# Bi_Dir_Circuit.net
KiCad netlist of a schematic drawn in Altium Designer
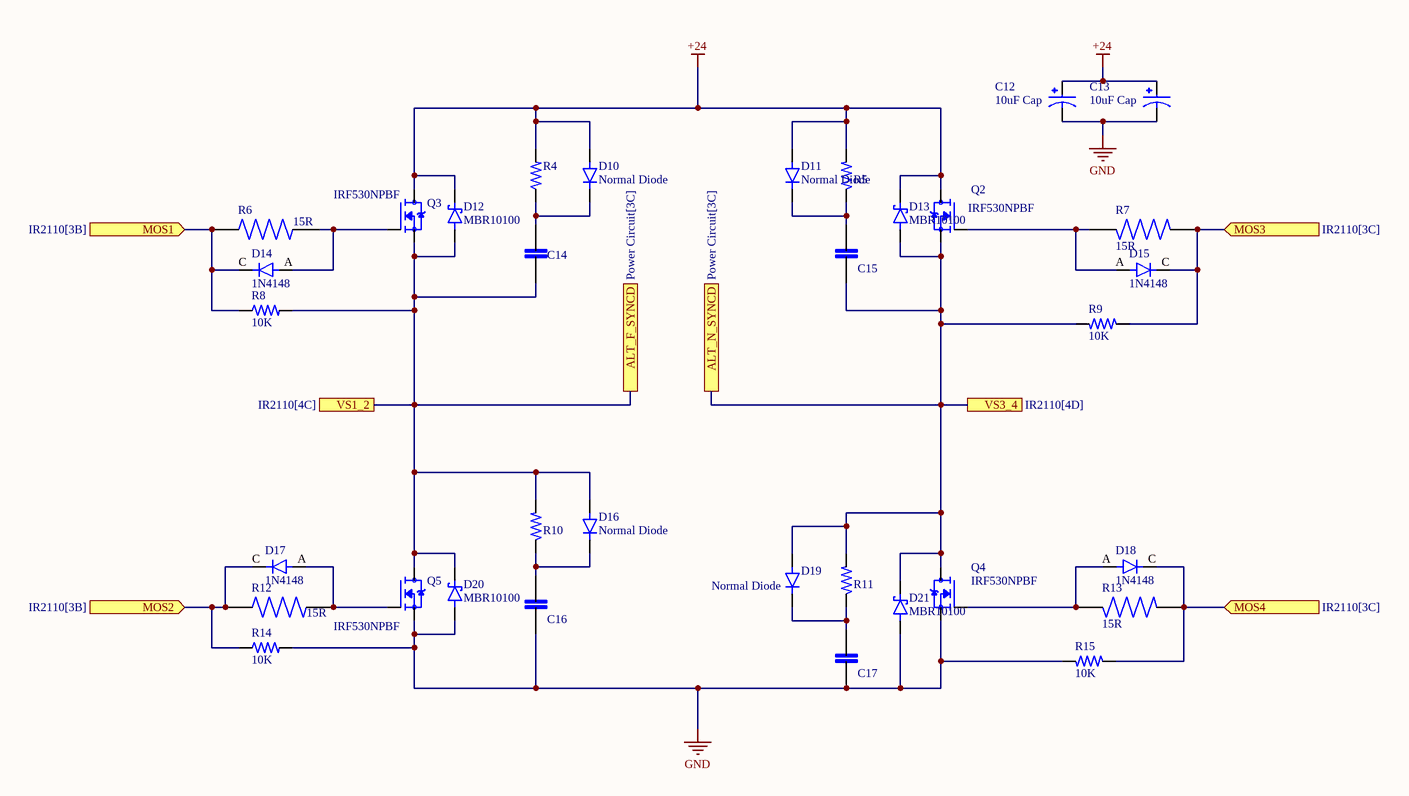
[diagram p0: Bi_Dir_Circuit.SchDoc]

(export (version "E")
  (design (tool "Eeschema 10.0.6"))
  (components
    (comp (ref "C12")
      (value "10uF Cap")
      (footprint "2200uF_Cap")
      (description "CAP ALUM 10UF 20% 50V RADIAL")
      (fields (field (name "MP") "ECE-A1HN100UI") (field (name "MF") "Panasonic"))
      (libsource (lib "MySCH_Library") (part "10uF Cap"))
    )
    (comp (ref "C13")
      (value "10uF Cap")
      (footprint "2200uF_Cap")
      (description "CAP ALUM 10UF 20% 50V RADIAL")
      (fields (field (name "MP") "ECE-A1HN100UI") (field (name "MF") "Panasonic"))
      (libsource (lib "MySCH_Library") (part "10uF Cap"))
    )
    (comp (ref "C14")
      (value "Ceramic Capacitor")
      (footprint "Ceramic Capacitor")
      (fields (field (name "MP") "LD051A121KAB2A") (field (name "MF") "AVX"))
      (libsource (lib "") (part "Ceramic Capacitor_1"))
    )
    (comp (ref "C15")
      (value "Ceramic Capacitor")
      (footprint "Ceramic Capacitor")
      (fields (field (name "MP") "LD051A121KAB2A") (field (name "MF") "AVX"))
      (libsource (lib "Capacitors Through Hole") (part "Ceramic Capacitor"))
    )
    (comp (ref "C16")
      (value "Ceramic Capacitor")
      (footprint "Ceramic Capacitor")
      (fields (field (name "MP") "LD051A121KAB2A") (field (name "MF") "AVX"))
      (libsource (lib "Capacitors Through Hole") (part "Ceramic Capacitor"))
    )
    (comp (ref "C17")
      (value "Ceramic Capacitor")
      (footprint "Ceramic Capacitor")
      (fields (field (name "MP") "LD051A121KAB2A") (field (name "MF") "AVX"))
      (libsource (lib "Capacitors Through Hole") (part "Ceramic Capacitor"))
    )
    (comp (ref "D10")
      (value "Normal Diode")
      (footprint "Common Trhough Hole")
      (fields (field (name "MF") "NTE Electronics, Inc.") (field (name "MP") "1N4007"))
      (libsource (lib "Diodes Through Hole") (part "Normal Diode"))
    )
    (comp (ref "D11")
      (value "Normal Diode")
      (footprint "Common Trhough Hole")
      (fields (field (name "MF") "NTE Electronics, Inc.") (field (name "MP") "1N4007"))
      (libsource (lib "Diodes Through Hole") (part "Normal Diode"))
    )
    (comp (ref "D12")
      (value "MBR10100")
      (footprint "MBR10100")
      (fields (field (name "MF") "Diodes Inc.") (field (name "MP") "1N5817-T"))
      (libsource (lib "Diodes Through Hole") (part "MBR10100"))
    )
    (comp (ref "D13")
      (value "MBR10100")
      (footprint "MBR10100")
      (fields (field (name "MF") "Diodes Inc.") (field (name "MP") "1N5817-T"))
      (libsource (lib "Diodes Through Hole") (part "MBR10100"))
    )
    (comp (ref "D14")
      (value "1N4148")
      (footprint "1N4007 DIODE")
      (description "Diode Standard 1000 V 1A Through Hole DO-41")
      (fields (field (name "MF") "NTE Electronics, Inc.") (field (name "MP") "1N4007"))
      (libsource (lib "MySCH_Library") (part "1N4007"))
    )
    (comp (ref "D15")
      (value "1N4148")
      (footprint "1N4007 DIODE")
      (description "Diode Standard 1000 V 1A Through Hole DO-41")
      (fields (field (name "MF") "NTE Electronics, Inc.") (field (name "MP") "1N4007"))
      (libsource (lib "MySCH_Library") (part "1N4007"))
    )
    (comp (ref "D16")
      (value "Normal Diode")
      (footprint "Common Trhough Hole")
      (fields (field (name "MF") "NTE Electronics, Inc.") (field (name "MP") "1N4007"))
      (libsource (lib "Diodes Through Hole") (part "Normal Diode"))
    )
    (comp (ref "D17")
      (value "1N4148")
      (footprint "1N4007 DIODE")
      (description "Diode Standard 1000 V 1A Through Hole DO-41")
      (fields (field (name "MF") "NTE Electronics, Inc.") (field (name "MP") "1N4007"))
      (libsource (lib "MySCH_Library") (part "1N4007"))
    )
    (comp (ref "D18")
      (value "1N4148")
      (footprint "1N4007 DIODE")
      (description "Diode Standard 1000 V 1A Through Hole DO-41")
      (fields (field (name "MF") "NTE Electronics, Inc.") (field (name "MP") "1N4007"))
      (libsource (lib "MySCH_Library") (part "1N4007"))
    )
    (comp (ref "D19")
      (value "Normal Diode")
      (footprint "Common Trhough Hole")
      (fields (field (name "MF") "NTE Electronics, Inc.") (field (name "MP") "1N4007"))
      (libsource (lib "Diodes Through Hole") (part "Normal Diode"))
    )
    (comp (ref "D20")
      (value "MBR10100")
      (footprint "MBR10100")
      (fields (field (name "MF") "Diodes Inc.") (field (name "MP") "1N5817-T"))
      (libsource (lib "Diodes Through Hole") (part "MBR10100"))
    )
    (comp (ref "D21")
      (value "MBR10100")
      (footprint "MBR10100")
      (fields (field (name "MF") "Diodes Inc.") (field (name "MP") "1N5817-T"))
      (libsource (lib "Diodes Through Hole") (part "MBR10100"))
    )
    (comp (ref "Q2")
      (value "IRF530NPBF")
      (footprint "IRF530N")
      (fields (field (name "MF") "Infineon Technologies"))
      (libsource (lib "MySCH_Library") (part "IRF530NPBF"))
    )
    (comp (ref "Q3")
      (value "IRF530NPBF")
      (footprint "IRF530N")
      (fields (field (name "MF") "Infineon Technologies"))
      (libsource (lib "MySCH_Library") (part "IRF530NPBF"))
    )
    (comp (ref "Q4")
      (value "IRF530NPBF")
      (footprint "IRF530N")
      (fields (field (name "MF") "Infineon Technologies"))
      (libsource (lib "MySCH_Library") (part "IRF530NPBF"))
    )
    (comp (ref "Q5")
      (value "IRF530NPBF")
      (footprint "IRF530N")
      (fields (field (name "MF") "Infineon Technologies"))
      (libsource (lib "MySCH_Library") (part "IRF530NPBF"))
    )
    (comp (ref "R4")
      (value "Resistor")
      (footprint "Resistor_Through Hole")
      (fields
        (field (name "MP") "2-2176053-0")
        (field (name "TOLERANCE") "1%")
        (field (name "MF") "TE Connectivity")
      )
      (libsource (lib "Resistors Through Hole") (part "Resistor"))
    )
    (comp (ref "R5")
      (value "Resistor")
      (footprint "Resistor_Through Hole")
      (fields
        (field (name "MP") "2-2176053-0")
        (field (name "TOLERANCE") "1%")
        (field (name "MF") "TE Connectivity")
      )
      (libsource (lib "Resistors Through Hole") (part "Resistor"))
    )
    (comp (ref "R6")
      (value "15R")
      (footprint "Resistor_Through Hole")
      (description "1.02 Ohms Â±1% 0.25W, 1/4W Through Hole Resistor Axial Metal Film")
      (fields (field (name "MP") "MFR-25FTE52-1R") (field (name "MF") "Yageo"))
      (libsource (lib "MySCH_Library") (part "Resistor_Through Hole"))
    )
    (comp (ref "R7")
      (value "15R")
      (footprint "Resistor_Through Hole")
      (description "1.02 Ohms Â±1% 0.25W, 1/4W Through Hole Resistor Axial Metal Film")
      (fields (field (name "MP") "MFR-25FTE52-1R") (field (name "MF") "Yageo"))
      (libsource (lib "MySCH_Library") (part "Resistor_Through Hole"))
    )
    (comp (ref "R8")
      (value "10K")
      (footprint "Resistor_Through Hole")
      (fields
        (field (name "MP") "2-2176053-0")
        (field (name "TOLERANCE") "1%")
        (field (name "MF") "TE Connectivity")
      )
      (libsource (lib "Resistors Through Hole") (part "Resistor"))
    )
    (comp (ref "R9")
      (value "10K")
      (footprint "Resistor_Through Hole")
      (fields
        (field (name "MP") "2-2176053-0")
        (field (name "TOLERANCE") "1%")
        (field (name "MF") "TE Connectivity")
      )
      (libsource (lib "Resistors Through Hole") (part "Resistor"))
    )
    (comp (ref "R10")
      (value "Resistor")
      (footprint "Resistor_Through Hole")
      (fields
        (field (name "MP") "2-2176053-0")
        (field (name "TOLERANCE") "1%")
        (field (name "MF") "TE Connectivity")
      )
      (libsource (lib "Resistors Through Hole") (part "Resistor"))
    )
    (comp (ref "R11")
      (value "Resistor")
      (footprint "Resistor_Through Hole")
      (fields
        (field (name "MP") "2-2176053-0")
        (field (name "TOLERANCE") "1%")
        (field (name "MF") "TE Connectivity")
      )
      (libsource (lib "Resistors Through Hole") (part "Resistor"))
    )
    (comp (ref "R12")
      (value "15R")
      (footprint "Resistor_Through Hole")
      (description "1.02 Ohms Â±1% 0.25W, 1/4W Through Hole Resistor Axial Metal Film")
      (fields (field (name "MP") "MFR-25FTE52-1R") (field (name "MF") "Yageo"))
      (libsource (lib "MySCH_Library") (part "Resistor_Through Hole"))
    )
    (comp (ref "R13")
      (value "15R")
      (footprint "Resistor_Through Hole")
      (description "1.02 Ohms Â±1% 0.25W, 1/4W Through Hole Resistor Axial Metal Film")
      (fields (field (name "MP") "MFR-25FTE52-1R") (field (name "MF") "Yageo"))
      (libsource (lib "MySCH_Library") (part "Resistor_Through Hole"))
    )
    (comp (ref "R14")
      (value "10K")
      (footprint "Resistor_Through Hole")
      (fields
        (field (name "MP") "2-2176053-0")
        (field (name "TOLERANCE") "1%")
        (field (name "MF") "TE Connectivity")
      )
      (libsource (lib "Resistors Through Hole") (part "Resistor"))
    )
    (comp (ref "R15")
      (value "10K")
      (footprint "Resistor_Through Hole")
      (fields
        (field (name "MP") "2-2176053-0")
        (field (name "TOLERANCE") "1%")
        (field (name "MF") "TE Connectivity")
      )
      (libsource (lib "Resistors Through Hole") (part "Resistor"))
    )
  )
  (nets
    (net (code "1") (name "+24") (class "Default")
      (node (ref "C12") (pin "P") (pinfunction "P_P") (pintype "passive"))
      (node (ref "C13") (pin "P") (pinfunction "P_P") (pintype "passive"))
      (node (ref "D10") (pin "2") (pinfunction "A_2") (pintype "passive"))
      (node (ref "D11") (pin "2") (pinfunction "A_2") (pintype "passive"))
      (node (ref "D12") (pin "1") (pinfunction "K_1") (pintype "passive"))
      (node (ref "D13") (pin "1") (pinfunction "K_1") (pintype "passive"))
      (node (ref "Q2") (pin "2") (pinfunction "D_2") (pintype "passive"))
      (node (ref "Q3") (pin "2") (pinfunction "D_2") (pintype "passive"))
      (node (ref "R4") (pin "2") (pinfunction "2_2") (pintype "passive"))
      (node (ref "R5") (pin "2") (pinfunction "2_2") (pintype "passive"))
    )
    (net (code "2") (name "/ALT_F_SYNCD") (class "Default")
      (node (ref "C14") (pin "1") (pinfunction "1_1") (pintype "passive"))
      (node (ref "D12") (pin "3") (pinfunction "A_3") (pintype "passive"))
      (node (ref "D16") (pin "2") (pinfunction "A_2") (pintype "passive"))
      (node (ref "D20") (pin "1") (pinfunction "K_1") (pintype "passive"))
      (node (ref "Q3") (pin "3") (pinfunction "S_3") (pintype "passive"))
      (node (ref "Q5") (pin "2") (pinfunction "D_2") (pintype "passive"))
      (node (ref "R10") (pin "2") (pinfunction "2_2") (pintype "passive"))
      (node (ref "R8") (pin "2") (pinfunction "2_2") (pintype "passive"))
    )
    (net (code "3") (name "/ALT_N_SYNCD") (class "Default")
      (node (ref "C15") (pin "1") (pinfunction "1_1") (pintype "passive"))
      (node (ref "D13") (pin "3") (pinfunction "A_3") (pintype "passive"))
      (node (ref "D19") (pin "2") (pinfunction "A_2") (pintype "passive"))
      (node (ref "D21") (pin "1") (pinfunction "K_1") (pintype "passive"))
      (node (ref "Q2") (pin "3") (pinfunction "S_3") (pintype "passive"))
      (node (ref "Q4") (pin "2") (pinfunction "D_2") (pintype "passive"))
      (node (ref "R11") (pin "2") (pinfunction "2_2") (pintype "passive"))
      (node (ref "R9") (pin "2") (pinfunction "2_2") (pintype "passive"))
    )
    (net (code "4") (name "/MOS1") (class "Default")
      (node (ref "D14") (pin "C") (pinfunction "C_C") (pintype "passive"))
      (node (ref "R6") (pin "1") (pinfunction "1_1") (pintype "passive"))
      (node (ref "R8") (pin "1") (pinfunction "1_1") (pintype "passive"))
    )
    (net (code "5") (name "/MOS2") (class "Default")
      (node (ref "D17") (pin "C") (pinfunction "C_C") (pintype "passive"))
      (node (ref "R12") (pin "1") (pinfunction "1_1") (pintype "passive"))
      (node (ref "R14") (pin "1") (pinfunction "1_1") (pintype "passive"))
    )
    (net (code "6") (name "/MOS3") (class "Default")
      (node (ref "D15") (pin "C") (pinfunction "C_C") (pintype "passive"))
      (node (ref "R7") (pin "1") (pinfunction "1_1") (pintype "passive"))
      (node (ref "R9") (pin "1") (pinfunction "1_1") (pintype "passive"))
    )
    (net (code "7") (name "/MOS4") (class "Default")
      (node (ref "D18") (pin "C") (pinfunction "C_C") (pintype "passive"))
      (node (ref "R13") (pin "1") (pinfunction "1_1") (pintype "passive"))
      (node (ref "R15") (pin "1") (pinfunction "1_1") (pintype "passive"))
    )
    (net (code "8") (name "GND") (class "Default")
      (node (ref "C12") (pin "N") (pinfunction "N_N") (pintype "passive"))
      (node (ref "C13") (pin "N") (pinfunction "N_N") (pintype "passive"))
      (node (ref "C16") (pin "1") (pinfunction "1_1") (pintype "passive"))
      (node (ref "C17") (pin "1") (pinfunction "1_1") (pintype "passive"))
      (node (ref "D20") (pin "3") (pinfunction "A_3") (pintype "passive"))
      (node (ref "D21") (pin "3") (pinfunction "A_3") (pintype "passive"))
      (node (ref "Q4") (pin "3") (pinfunction "S_3") (pintype "passive"))
      (node (ref "Q5") (pin "3") (pinfunction "S_3") (pintype "passive"))
      (node (ref "R14") (pin "2") (pinfunction "2_2") (pintype "passive"))
      (node (ref "R15") (pin "2") (pinfunction "2_2") (pintype "passive"))
    )
    (net (code "9") (name "Net-(D10-K)") (class "Default")
      (node (ref "C14") (pin "2") (pinfunction "2_2") (pintype "passive"))
      (node (ref "D10") (pin "1") (pinfunction "K_1") (pintype "passive"))
      (node (ref "R4") (pin "1") (pinfunction "1_1") (pintype "passive"))
    )
    (net (code "10") (name "Net-(D11-K)") (class "Default")
      (node (ref "C15") (pin "2") (pinfunction "2_2") (pintype "passive"))
      (node (ref "D11") (pin "1") (pinfunction "K_1") (pintype "passive"))
      (node (ref "R5") (pin "1") (pinfunction "1_1") (pintype "passive"))
    )
    (net (code "11") (name "Net-(D16-K)") (class "Default")
      (node (ref "C16") (pin "2") (pinfunction "2_2") (pintype "passive"))
      (node (ref "D16") (pin "1") (pinfunction "K_1") (pintype "passive"))
      (node (ref "R10") (pin "1") (pinfunction "1_1") (pintype "passive"))
    )
    (net (code "12") (name "Net-(D19-K)") (class "Default")
      (node (ref "C17") (pin "2") (pinfunction "2_2") (pintype "passive"))
      (node (ref "D19") (pin "1") (pinfunction "K_1") (pintype "passive"))
      (node (ref "R11") (pin "1") (pinfunction "1_1") (pintype "passive"))
    )
    (net (code "13") (name "Net-(Q2-G)") (class "Default")
      (node (ref "D15") (pin "A") (pinfunction "A_A") (pintype "passive"))
      (node (ref "Q2") (pin "1") (pinfunction "G_1") (pintype "passive"))
      (node (ref "R7") (pin "2") (pinfunction "2_2") (pintype "passive"))
    )
    (net (code "14") (name "Net-(Q3-G)") (class "Default")
      (node (ref "D14") (pin "A") (pinfunction "A_A") (pintype "passive"))
      (node (ref "Q3") (pin "1") (pinfunction "G_1") (pintype "passive"))
      (node (ref "R6") (pin "2") (pinfunction "2_2") (pintype "passive"))
    )
    (net (code "15") (name "Net-(Q4-G)") (class "Default")
      (node (ref "D18") (pin "A") (pinfunction "A_A") (pintype "passive"))
      (node (ref "Q4") (pin "1") (pinfunction "G_1") (pintype "passive"))
      (node (ref "R13") (pin "2") (pinfunction "2_2") (pintype "passive"))
    )
    (net (code "16") (name "Net-(Q5-G)") (class "Default")
      (node (ref "D17") (pin "A") (pinfunction "A_A") (pintype "passive"))
      (node (ref "Q5") (pin "1") (pinfunction "G_1") (pintype "passive"))
      (node (ref "R12") (pin "2") (pinfunction "2_2") (pintype "passive"))
    )
  )
)
